# Power_module.net
KiCad netlist of a schematic drawn in Altium Designer
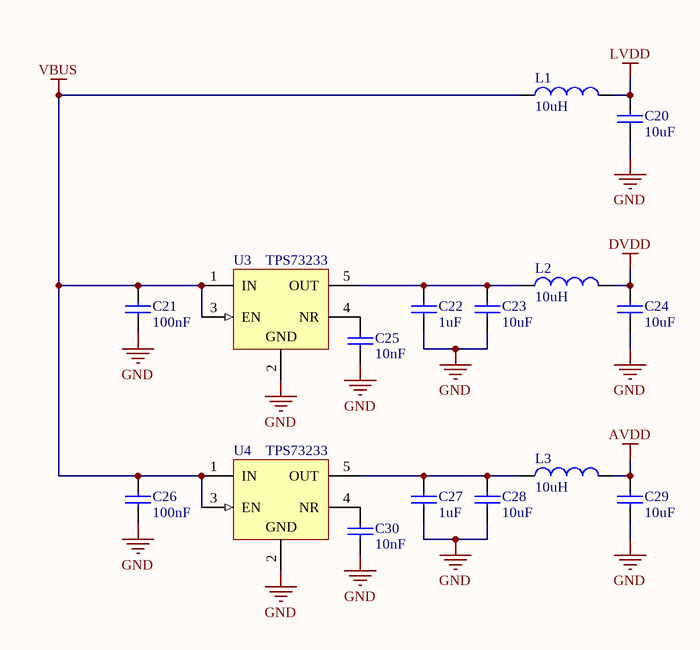
[diagram p0: Power_module.SchDoc]

(export (version "E")
  (design (tool "Eeschema 10.0.6"))
  (components
    (comp (ref "C20")
      (value "10uF")
      (footprint "6-0805_M")
      (description "Capacitor")
      (fields (field (name "Comment") "Cap") (field (name "PUBLISHER") "Altium Limited"))
      (libsource (lib "Miscellaneous Devices") (part "Cap"))
    )
    (comp (ref "C21")
      (value "100nF")
      (footprint "6-0805_M")
      (description "Capacitor")
      (fields (field (name "Comment") "Cap") (field (name "PUBLISHER") "Altium Limited"))
      (libsource (lib "Miscellaneous Devices") (part "Cap"))
    )
    (comp (ref "C22")
      (value "1uF")
      (footprint "6-0805_M")
      (description "Capacitor")
      (fields (field (name "Comment") "Cap") (field (name "PUBLISHER") "Altium Limited"))
      (libsource (lib "Miscellaneous Devices") (part "Cap"))
    )
    (comp (ref "C23")
      (value "10uF")
      (footprint "6-0805_M")
      (description "Capacitor")
      (fields (field (name "Comment") "Cap") (field (name "PUBLISHER") "Altium Limited"))
      (libsource (lib "Miscellaneous Devices") (part "Cap"))
    )
    (comp (ref "C24")
      (value "10uF")
      (footprint "6-0805_M")
      (description "Capacitor")
      (fields (field (name "Comment") "Cap") (field (name "PUBLISHER") "Altium Limited"))
      (libsource (lib "Miscellaneous Devices") (part "Cap"))
    )
    (comp (ref "C25")
      (value "10nF")
      (footprint "6-0805_M")
      (description "Capacitor")
      (fields (field (name "Comment") "Cap") (field (name "PUBLISHER") "Altium Limited"))
      (libsource (lib "Miscellaneous Devices") (part "Cap"))
    )
    (comp (ref "C26")
      (value "100nF")
      (footprint "6-0805_M")
      (description "Capacitor")
      (fields (field (name "Comment") "Cap") (field (name "PUBLISHER") "Altium Limited"))
      (libsource (lib "Miscellaneous Devices") (part "Cap"))
    )
    (comp (ref "C27")
      (value "1uF")
      (footprint "6-0805_M")
      (description "Capacitor")
      (fields (field (name "Comment") "Cap") (field (name "PUBLISHER") "Altium Limited"))
      (libsource (lib "Miscellaneous Devices") (part "Cap"))
    )
    (comp (ref "C28")
      (value "10uF")
      (footprint "6-0805_M")
      (description "Capacitor")
      (fields (field (name "Comment") "Cap") (field (name "PUBLISHER") "Altium Limited"))
      (libsource (lib "Miscellaneous Devices") (part "Cap"))
    )
    (comp (ref "C29")
      (value "10uF")
      (footprint "6-0805_M")
      (description "Capacitor")
      (fields (field (name "Comment") "Cap") (field (name "PUBLISHER") "Altium Limited"))
      (libsource (lib "Miscellaneous Devices") (part "Cap"))
    )
    (comp (ref "C30")
      (value "10nF")
      (footprint "6-0805_M")
      (description "Capacitor")
      (fields (field (name "Comment") "Cap") (field (name "PUBLISHER") "Altium Limited"))
      (libsource (lib "Miscellaneous Devices") (part "Cap"))
    )
    (comp (ref "L1")
      (value "10uH")
      (footprint "6-0805_M")
      (description "Inductor")
      (fields (field (name "PUBLISHER") "Altium Limited"))
      (libsource (lib "Miscellaneous Devices") (part "Inductor"))
    )
    (comp (ref "L2")
      (value "10uH")
      (footprint "6-0805_M")
      (description "Inductor")
      (fields (field (name "PUBLISHER") "Altium Limited"))
      (libsource (lib "Miscellaneous Devices") (part "Inductor"))
    )
    (comp (ref "L3")
      (value "10uH")
      (footprint "6-0805_M")
      (description "Inductor")
      (fields (field (name "PUBLISHER") "Altium Limited"))
      (libsource (lib "Miscellaneous Devices") (part "Inductor"))
    )
    (comp (ref "U3")
      (value "TPS73233")
      (footprint "TI-DBV5_N")
      (fields (field (name "MANUFACTURER") "Texas Instruments") (field (name "PARTNUMBER") "TPS73233DBVT"))
      (libsource (lib "TI Power Management Linear Regulator Single Channel LDO (0-350mA)") (part "TPS73233DBVT"))
    )
    (comp (ref "U4")
      (value "TPS73233")
      (footprint "TI-DBV5_N")
      (fields (field (name "MANUFACTURER") "Texas Instruments") (field (name "PARTNUMBER") "TPS73233DBVT"))
      (libsource (lib "TI Power Management Linear Regulator Single Channel LDO (0-350mA)") (part "TPS73233DBVT"))
    )
  )
  (nets
    (net (code "1") (name "AVDD") (class "Default")
      (node (ref "C29") (pin "2") (pinfunction "2_2") (pintype "passive"))
      (node (ref "L3") (pin "2") (pinfunction "2_2") (pintype "passive"))
    )
    (net (code "2") (name "DVDD") (class "Default")
      (node (ref "C24") (pin "2") (pinfunction "2_2") (pintype "passive"))
      (node (ref "L2") (pin "2") (pinfunction "2_2") (pintype "passive"))
    )
    (net (code "3") (name "GND") (class "Default")
      (node (ref "C20") (pin "1") (pinfunction "1_1") (pintype "passive"))
      (node (ref "C21") (pin "1") (pinfunction "1_1") (pintype "passive"))
      (node (ref "C22") (pin "1") (pinfunction "1_1") (pintype "passive"))
      (node (ref "C23") (pin "1") (pinfunction "1_1") (pintype "passive"))
      (node (ref "C24") (pin "1") (pinfunction "1_1") (pintype "passive"))
      (node (ref "C25") (pin "1") (pinfunction "1_1") (pintype "passive"))
      (node (ref "C26") (pin "1") (pinfunction "1_1") (pintype "passive"))
      (node (ref "C27") (pin "1") (pinfunction "1_1") (pintype "passive"))
      (node (ref "C28") (pin "1") (pinfunction "1_1") (pintype "passive"))
      (node (ref "C29") (pin "1") (pinfunction "1_1") (pintype "passive"))
      (node (ref "C30") (pin "1") (pinfunction "1_1") (pintype "passive"))
      (node (ref "U3") (pin "2") (pinfunction "GND_2") (pintype "power_in"))
      (node (ref "U4") (pin "2") (pinfunction "GND_2") (pintype "power_in"))
    )
    (net (code "4") (name "LVDD") (class "Default")
      (node (ref "C20") (pin "2") (pinfunction "2_2") (pintype "passive"))
      (node (ref "L1") (pin "2") (pinfunction "2_2") (pintype "passive"))
    )
    (net (code "5") (name "Net-(U3-NR)") (class "Default")
      (node (ref "C25") (pin "2") (pinfunction "2_2") (pintype "passive"))
      (node (ref "U3") (pin "4") (pinfunction "NR_4") (pintype "passive"))
    )
    (net (code "6") (name "Net-(U3-OUT)") (class "Default")
      (node (ref "C22") (pin "2") (pinfunction "2_2") (pintype "passive"))
      (node (ref "C23") (pin "2") (pinfunction "2_2") (pintype "passive"))
      (node (ref "L2") (pin "1") (pinfunction "1_1") (pintype "passive"))
      (node (ref "U3") (pin "5") (pinfunction "OUT_5") (pintype "power_in"))
    )
    (net (code "7") (name "Net-(U4-NR)") (class "Default")
      (node (ref "C30") (pin "2") (pinfunction "2_2") (pintype "passive"))
      (node (ref "U4") (pin "4") (pinfunction "NR_4") (pintype "passive"))
    )
    (net (code "8") (name "Net-(U4-OUT)") (class "Default")
      (node (ref "C27") (pin "2") (pinfunction "2_2") (pintype "passive"))
      (node (ref "C28") (pin "2") (pinfunction "2_2") (pintype "passive"))
      (node (ref "L3") (pin "1") (pinfunction "1_1") (pintype "passive"))
      (node (ref "U4") (pin "5") (pinfunction "OUT_5") (pintype "power_in"))
    )
    (net (code "9") (name "VBUS") (class "Default")
      (node (ref "C21") (pin "2") (pinfunction "2_2") (pintype "passive"))
      (node (ref "C26") (pin "2") (pinfunction "2_2") (pintype "passive"))
      (node (ref "L1") (pin "1") (pinfunction "1_1") (pintype "passive"))
      (node (ref "U3") (pin "1") (pinfunction "IN_1") (pintype "power_in"))
      (node (ref "U3") (pin "3") (pinfunction "EN_3") (pintype "input"))
      (node (ref "U4") (pin "1") (pinfunction "IN_1") (pintype "power_in"))
      (node (ref "U4") (pin "3") (pinfunction "EN_3") (pintype "input"))
    )
  )
)
